# isolation.net
KiCad netlist of a schematic drawn in EAGLE
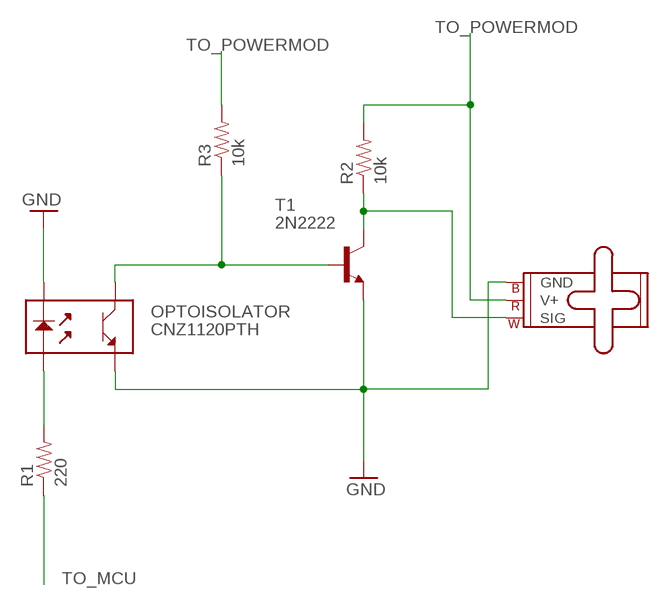
[diagram p0: schematic, sheet 1]

(export (version "E")
  (design (tool "Eeschema 10.0.6"))
  (components
    (comp (ref "M1")
      (value "SMALL_SERVO")
      (footprint "eagle-import:1X03")
      (libsource (lib "eagle-import") (part "SMALL_SERVO"))
    )
    (comp (ref "OPTOISOLATOR")
      (value "CNZ1120PTH")
      (footprint "eagle-import:CNZ1120")
      (libsource (lib "eagle-import") (part "CNZ1120PTH"))
    )
    (comp (ref "R1")
      (value "220")
      (footprint "eagle-import:AXIAL-0.3EZ")
      (libsource (lib "eagle-import") (part "RESISTOREZ"))
    )
    (comp (ref "R2")
      (value "10k")
      (footprint "eagle-import:AXIAL-0.3EZ")
      (libsource (lib "eagle-import") (part "RESISTOREZ"))
    )
    (comp (ref "R3")
      (value "10k")
      (footprint "eagle-import:AXIAL-0.3EZ")
      (libsource (lib "eagle-import") (part "RESISTOREZ"))
    )
    (comp (ref "T1")
      (value "2N2222")
      (footprint "eagle-import:TO92-EBC-OVAL")
      (libsource (lib "eagle-import") (part "2N2222"))
    )
  )
  (nets
    (net (code "1") (name "/TO_MCU") (class "Default")
      (node (ref "R1") (pin "P$1") (pinfunction "1_P$1") (pintype "passive"))
    )
    (net (code "2") (name "/TO_POWERMOD") (class "Default")
      (node (ref "M1") (pin "2") (pinfunction "V+_2") (pintype "bidirectional"))
      (node (ref "R2") (pin "P$2") (pinfunction "2_P$2") (pintype "passive"))
      (node (ref "R3") (pin "P$2") (pinfunction "2_P$2") (pintype "passive"))
    )
    (net (code "3") (name "GND") (class "Default")
      (node (ref "M1") (pin "3") (pinfunction "GND_3") (pintype "bidirectional"))
      (node (ref "OPTOISOLATOR") (pin "2") (pinfunction "2_2") (pintype "bidirectional"))
      (node (ref "OPTOISOLATOR") (pin "4") (pinfunction "4_4") (pintype "bidirectional"))
      (node (ref "T1") (pin "E") (pinfunction "E_E") (pintype "passive"))
    )
    (net (code "4") (name "Net-(M1-SIG)") (class "Default")
      (node (ref "M1") (pin "1") (pinfunction "SIG_1") (pintype "bidirectional"))
      (node (ref "R2") (pin "P$1") (pinfunction "1_P$1") (pintype "passive"))
      (node (ref "T1") (pin "C") (pinfunction "C_C") (pintype "passive"))
    )
    (net (code "5") (name "Net-(R1-2)") (class "Default")
      (node (ref "OPTOISOLATOR") (pin "1") (pinfunction "1_1") (pintype "bidirectional"))
      (node (ref "R1") (pin "P$2") (pinfunction "2_P$2") (pintype "passive"))
    )
    (net (code "6") (name "Net-(R3-1)") (class "Default")
      (node (ref "OPTOISOLATOR") (pin "3") (pinfunction "3_3") (pintype "bidirectional"))
      (node (ref "R3") (pin "P$1") (pinfunction "1_P$1") (pintype "passive"))
      (node (ref "T1") (pin "B") (pinfunction "B_B") (pintype "passive"))
    )
  )
)
